# MainCPCB003.net
KiCad netlist of a schematic drawn in EAGLE
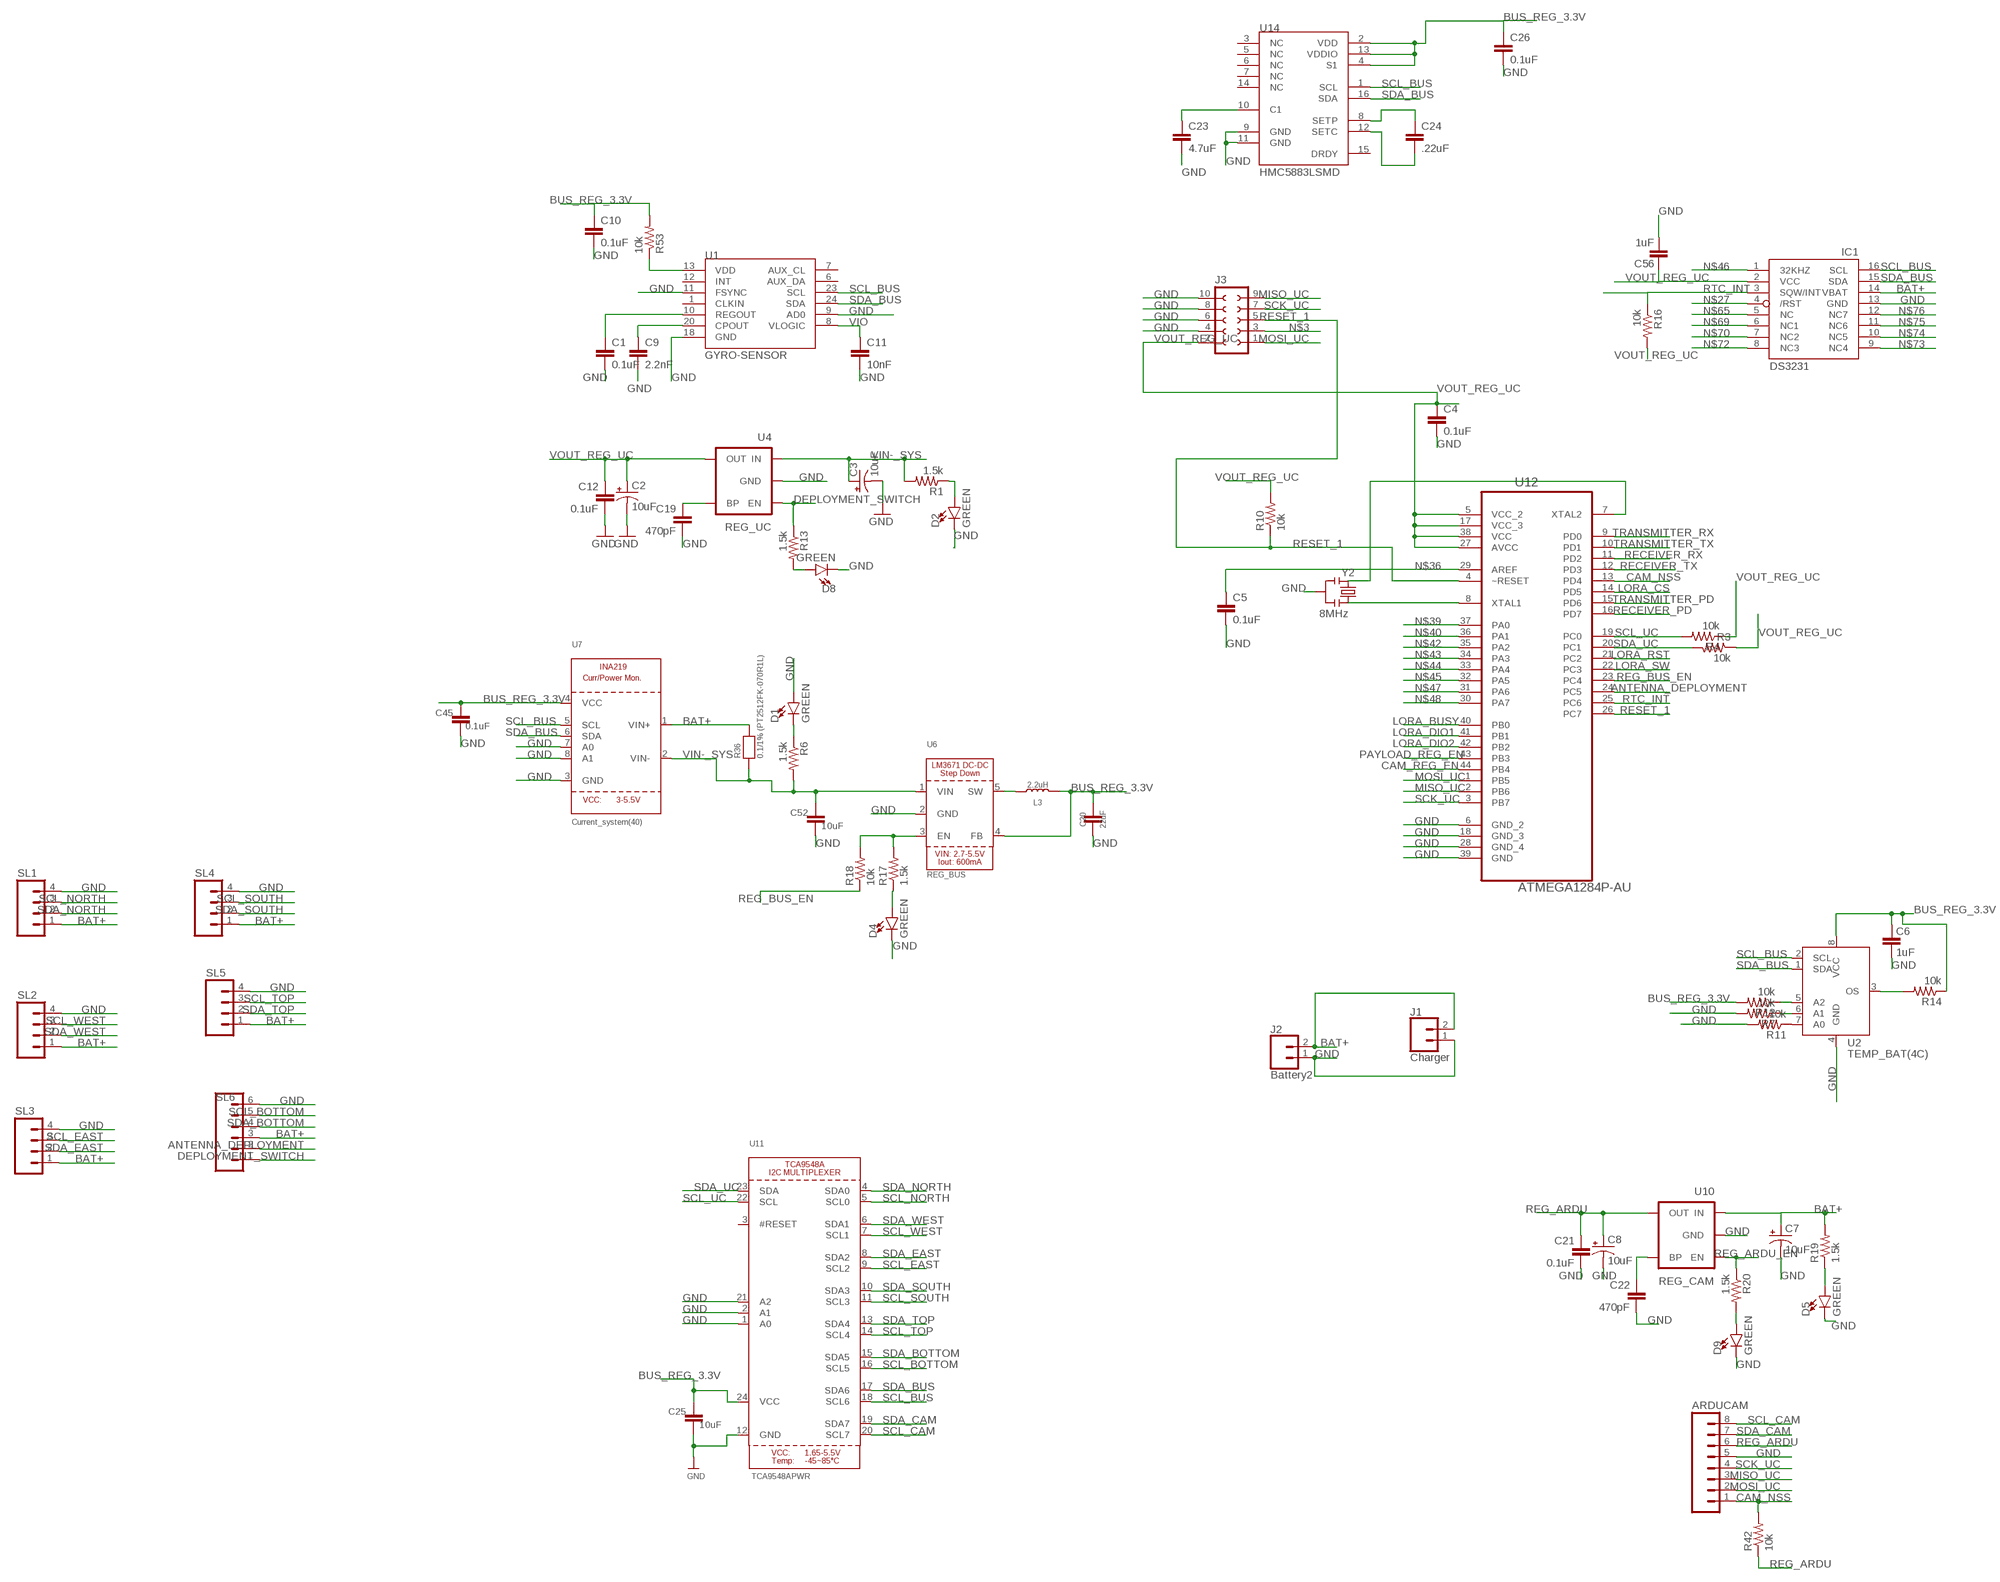
[diagram p0: schematic, sheet 1, part 1 of 2]
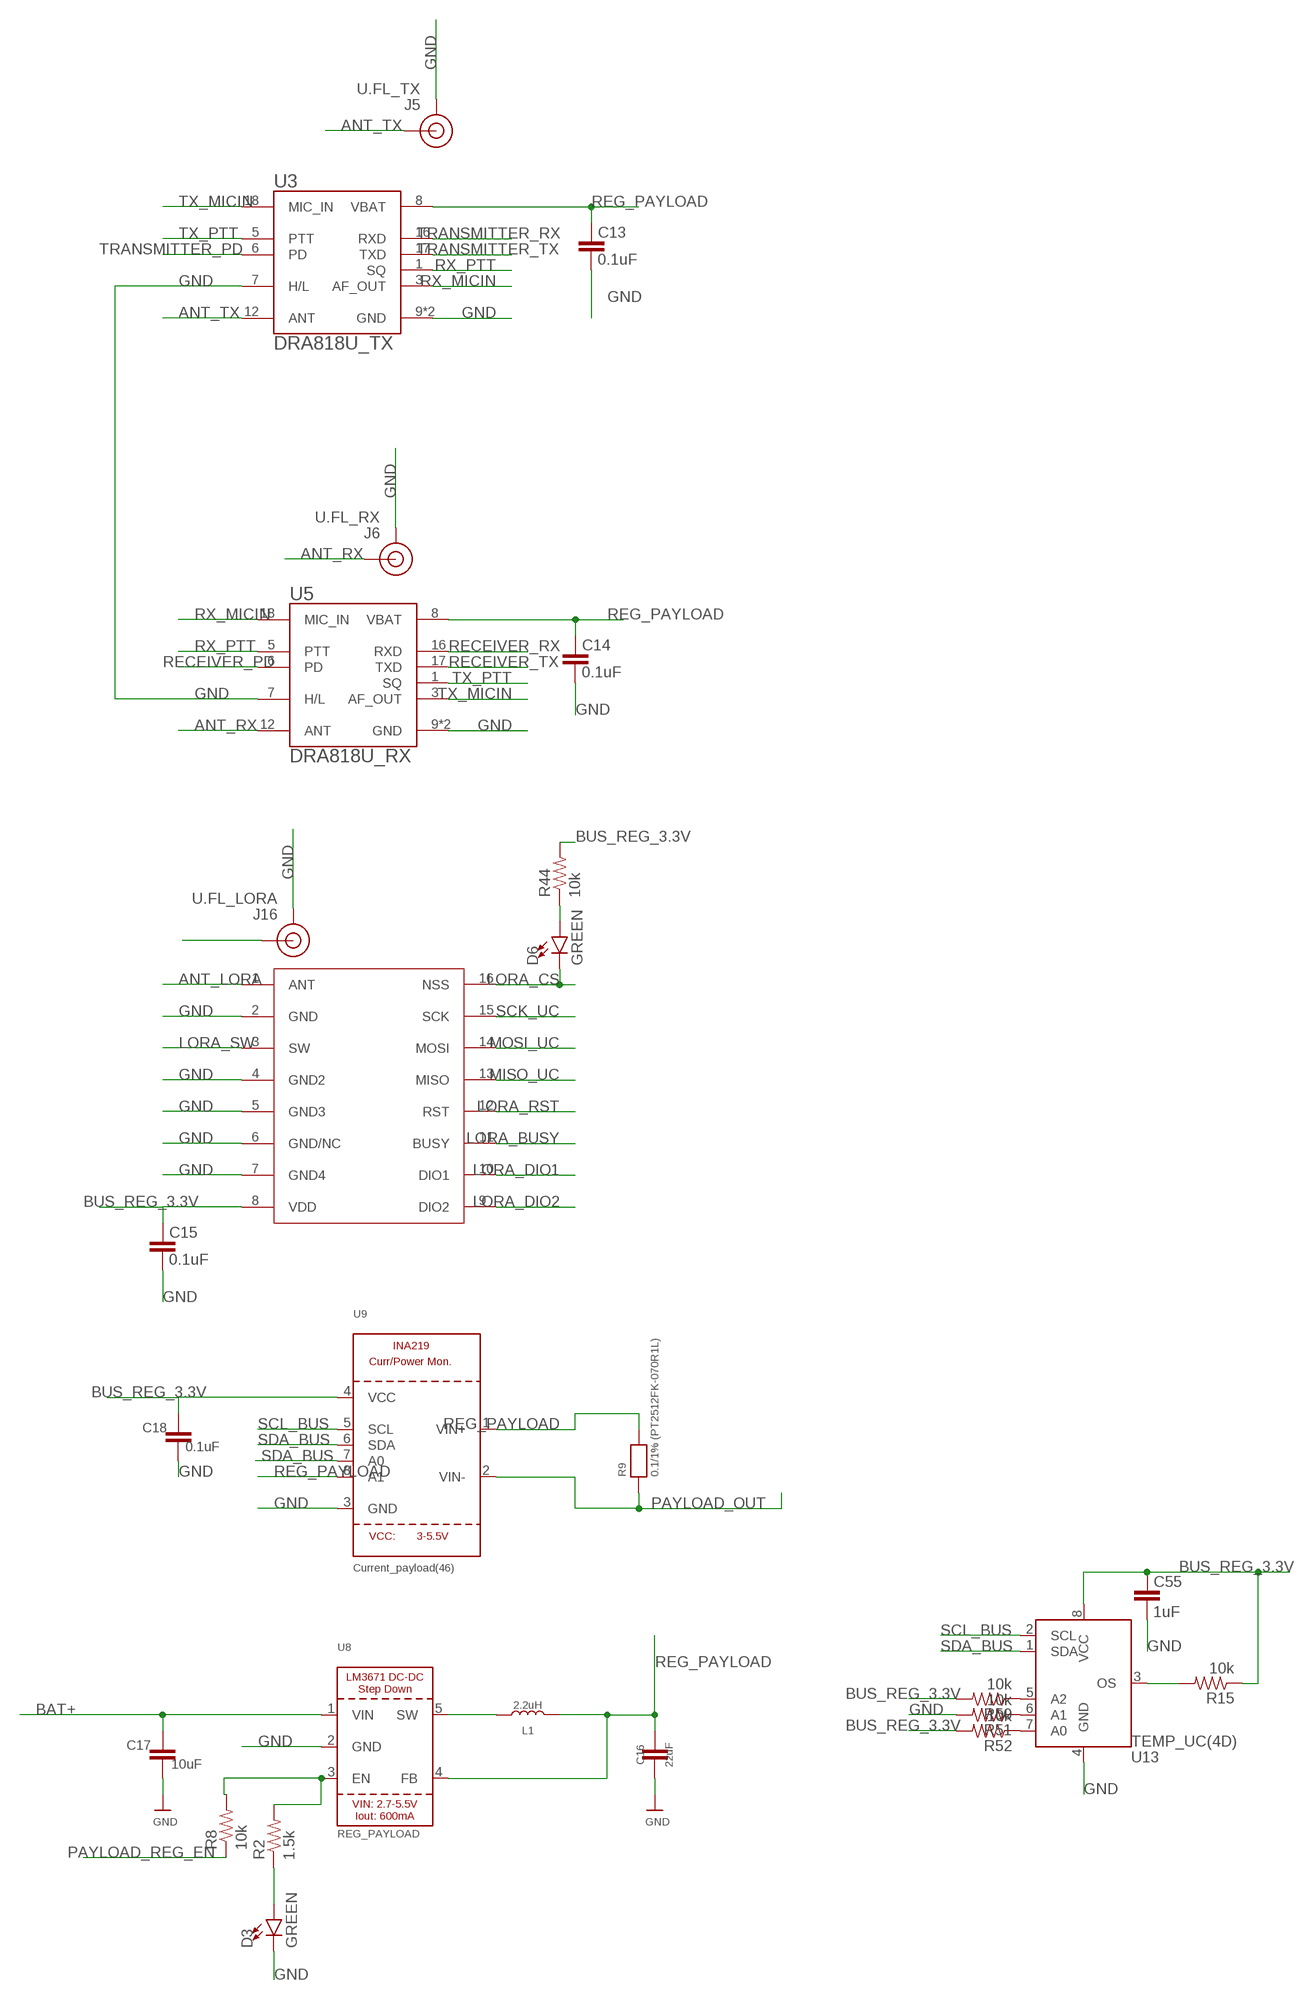
[diagram p1: schematic, sheet 1, part 2 of 2]

(export (version "E")
  (design (tool "Eeschema 10.0.6"))
  (components
    (comp (ref "ARDUCAM")
      (value "M08")
      (footprint "eagle-import:08P")
      (libsource (lib "eagle-import") (part "M08"))
    )
    (comp (ref "C1")
      (value "0.1uF")
      (footprint "eagle-import:0603-CAP")
      (libsource (lib "eagle-import") (part "CAP0603-CAP"))
    )
    (comp (ref "C2")
      (value "10uF")
      (footprint "eagle-import:0603-POLAR")
      (libsource (lib "eagle-import") (part "10UF-POLAR-0603-6.3V-20%(TANT)"))
    )
    (comp (ref "C3")
      (value "10uF")
      (footprint "eagle-import:0603-POLAR")
      (libsource (lib "eagle-import") (part "10UF-POLAR-0603-6.3V-20%(TANT)"))
    )
    (comp (ref "C4")
      (value "0.1uF")
      (footprint "eagle-import:0603-CAP")
      (libsource (lib "eagle-import") (part "CAP0603-CAP"))
    )
    (comp (ref "C5")
      (value "0.1uF")
      (footprint "eagle-import:0603-CAP")
      (libsource (lib "eagle-import") (part "CAP0603-CAP"))
    )
    (comp (ref "C6")
      (value "1uF")
      (footprint "eagle-import:0603-CAP")
      (libsource (lib "eagle-import") (part "CAP0603-CAP"))
    )
    (comp (ref "C7")
      (value "10uF")
      (footprint "eagle-import:0603-POLAR")
      (libsource (lib "eagle-import") (part "10UF-POLAR-0603-6.3V-20%(TANT)"))
    )
    (comp (ref "C8")
      (value "10uF")
      (footprint "eagle-import:0603-POLAR")
      (libsource (lib "eagle-import") (part "10UF-POLAR-0603-6.3V-20%(TANT)"))
    )
    (comp (ref "C9")
      (value "2.2nF")
      (footprint "eagle-import:0603-CAP")
      (libsource (lib "eagle-import") (part "CAP0603-CAP"))
    )
    (comp (ref "C10")
      (value "0.1uF")
      (footprint "eagle-import:0603-CAP")
      (libsource (lib "eagle-import") (part "CAP0603-CAP"))
    )
    (comp (ref "C11")
      (value "10nF")
      (footprint "eagle-import:0603-CAP")
      (libsource (lib "eagle-import") (part "CAP0603-CAP"))
    )
    (comp (ref "C12")
      (value "0.1uF")
      (footprint "eagle-import:0603-CAP")
      (libsource (lib "eagle-import") (part "CAP0603-CAP"))
    )
    (comp (ref "C13")
      (value "0.1uF")
      (footprint "eagle-import:0603-CAP")
      (libsource (lib "eagle-import") (part "CAP0603-CAP"))
    )
    (comp (ref "C14")
      (value "0.1uF")
      (footprint "eagle-import:0603-CAP")
      (libsource (lib "eagle-import") (part "CAP0603-CAP"))
    )
    (comp (ref "C15")
      (value "0.1uF")
      (footprint "eagle-import:0603-CAP")
      (libsource (lib "eagle-import") (part "CAP0603-CAP"))
    )
    (comp (ref "C16")
      (value "22uF")
      (footprint "eagle-import:0603")
      (libsource (lib "eagle-import") (part "10UF-0603-6.3V-20%"))
    )
    (comp (ref "C17")
      (value "10uF")
      (footprint "eagle-import:0603")
      (libsource (lib "eagle-import") (part "10UF-0603-6.3V-20%"))
    )
    (comp (ref "C18")
      (value "0.1uF")
      (footprint "eagle-import:0603")
      (libsource (lib "eagle-import") (part "10UF-0603-6.3V-20%"))
    )
    (comp (ref "C19")
      (value "470pF")
      (footprint "eagle-import:0603-CAP")
      (libsource (lib "eagle-import") (part "CAP0603-CAP"))
    )
    (comp (ref "C20")
      (value "22uF")
      (footprint "eagle-import:0603")
      (libsource (lib "eagle-import") (part "10UF-0603-6.3V-20%"))
    )
    (comp (ref "C21")
      (value "0.1uF")
      (footprint "eagle-import:0603-CAP")
      (libsource (lib "eagle-import") (part "CAP0603-CAP"))
    )
    (comp (ref "C22")
      (value "470pF")
      (footprint "eagle-import:0603-CAP")
      (libsource (lib "eagle-import") (part "CAP0603-CAP"))
    )
    (comp (ref "C23")
      (value "4.7uF")
      (footprint "eagle-import:0603")
      (libsource (lib "eagle-import") (part "0.18UF-0603-10V-10%"))
    )
    (comp (ref "C24")
      (value ".22uF")
      (footprint "eagle-import:0603")
      (libsource (lib "eagle-import") (part "0.18UF-0603-10V-10%"))
    )
    (comp (ref "C25")
      (value "10uF")
      (footprint "eagle-import:0603")
      (libsource (lib "eagle-import") (part "10UF-0603-6.3V-20%"))
    )
    (comp (ref "C26")
      (value "0.1uF")
      (footprint "eagle-import:0603")
      (libsource (lib "eagle-import") (part "0.18UF-0603-10V-10%"))
    )
    (comp (ref "C45")
      (value "0.1uF")
      (footprint "eagle-import:0603")
      (libsource (lib "eagle-import") (part "10UF-0603-6.3V-20%"))
    )
    (comp (ref "C52")
      (value "10uF")
      (footprint "eagle-import:0603")
      (libsource (lib "eagle-import") (part "10UF-0603-6.3V-20%"))
    )
    (comp (ref "C55")
      (value "1uF")
      (footprint "eagle-import:0603-CAP")
      (libsource (lib "eagle-import") (part "CAP0603-CAP"))
    )
    (comp (ref "C56")
      (value "1uF")
      (footprint "eagle-import:0603-CAP")
      (libsource (lib "eagle-import") (part "CAP0603-CAP"))
    )
    (comp (ref "D1")
      (value "GREEN")
      (footprint "eagle-import:LED-0603")
      (libsource (lib "eagle-import") (part "LED-GREEN0603"))
    )
    (comp (ref "D2")
      (value "GREEN")
      (footprint "eagle-import:LED-0603")
      (libsource (lib "eagle-import") (part "LED-GREEN0603"))
    )
    (comp (ref "D3")
      (value "GREEN")
      (footprint "eagle-import:LED-0603")
      (libsource (lib "eagle-import") (part "LED-GREEN0603"))
    )
    (comp (ref "D4")
      (value "GREEN")
      (footprint "eagle-import:LED-0603")
      (libsource (lib "eagle-import") (part "LED-GREEN0603"))
    )
    (comp (ref "D5")
      (value "GREEN")
      (footprint "eagle-import:LED-0603")
      (libsource (lib "eagle-import") (part "LED-GREEN0603"))
    )
    (comp (ref "D6")
      (value "GREEN")
      (footprint "eagle-import:LED-0603")
      (libsource (lib "eagle-import") (part "LED-GREEN0603"))
    )
    (comp (ref "D8")
      (value "GREEN")
      (footprint "eagle-import:LED-0603")
      (libsource (lib "eagle-import") (part "LED-GREEN0603"))
    )
    (comp (ref "D9")
      (value "GREEN")
      (footprint "eagle-import:LED-0603")
      (libsource (lib "eagle-import") (part "LED-GREEN0603"))
    )
    (comp (ref "IC1")
      (value "DS3231/SO")
      (footprint "eagle-import:SO16W")
      (fields (field (name "MF") "Maxim Integrated") (field (name "MP") "DS3231"))
      (libsource (lib "eagle-import") (part "DS3231/SO"))
    )
    (comp (ref "J1")
      (value "Charger")
      (footprint "eagle-import:1X02")
      (libsource (lib "eagle-import") (part "CONN_02"))
    )
    (comp (ref "J2")
      (value "Battery2")
      (footprint "eagle-import:1X02")
      (libsource (lib "eagle-import") (part "CONN_02"))
    )
    (comp (ref "J3")
      (value "SOCKET-10V")
      (footprint "eagle-import:S10V")
      (libsource (lib "eagle-import") (part "SOCKET-10V"))
    )
    (comp (ref "J5")
      (value "U.FL_TX")
      (footprint "eagle-import:U.FL")
      (libsource (lib "eagle-import") (part "U.FL2PIN"))
    )
    (comp (ref "J6")
      (value "U.FL_RX")
      (footprint "eagle-import:U.FL")
      (libsource (lib "eagle-import") (part "U.FL2PIN"))
    )
    (comp (ref "J16")
      (value "U.FL_LORA")
      (footprint "eagle-import:U.FL")
      (libsource (lib "eagle-import") (part "U.FL2PIN"))
    )
    (comp (ref "L1")
      (value "2.2uH")
      (footprint "eagle-import:0603")
      (libsource (lib "eagle-import") (part "INDUCTOR-0603-33NH"))
    )
    (comp (ref "L3")
      (value "2.2uH")
      (footprint "eagle-import:0603")
      (libsource (lib "eagle-import") (part "INDUCTOR-0603-33NH"))
    )
    (comp (ref "R1")
      (value "1.5k")
      (footprint "eagle-import:0603-RES")
      (libsource (lib "eagle-import") (part "RESISTOR0603-RES"))
    )
    (comp (ref "R2")
      (value "1.5k")
      (footprint "eagle-import:0603-RES")
      (libsource (lib "eagle-import") (part "RESISTOR0603-RES"))
    )
    (comp (ref "R3")
      (value "10k")
      (footprint "eagle-import:0603-RES")
      (libsource (lib "eagle-import") (part "RESISTOR0603-RES"))
    )
    (comp (ref "R4")
      (value "10k")
      (footprint "eagle-import:0603-RES")
      (libsource (lib "eagle-import") (part "RESISTOR0603-RES"))
    )
    (comp (ref "R6")
      (value "1.5k")
      (footprint "eagle-import:0603-RES")
      (libsource (lib "eagle-import") (part "RESISTOR0603-RES"))
    )
    (comp (ref "R7")
      (value "10k")
      (footprint "eagle-import:0603-RES")
      (libsource (lib "eagle-import") (part "RESISTOR0603-RES"))
    )
    (comp (ref "R8")
      (value "10k")
      (footprint "eagle-import:0402-RES")
      (libsource (lib "eagle-import") (part "RESISTOR0402-RES"))
    )
    (comp (ref "R9")
      (value "0.1/1% (PT2512FK-070R1L)")
      (footprint "eagle-import:2512")
      (libsource (lib "eagle-import") (part "microbuilder_RESISTOR2512"))
    )
    (comp (ref "R10")
      (value "10k")
      (footprint "eagle-import:0402-RES")
      (libsource (lib "eagle-import") (part "RESISTOR0402-RES"))
    )
    (comp (ref "R11")
      (value "10k")
      (footprint "eagle-import:0603-RES")
      (libsource (lib "eagle-import") (part "RESISTOR0603-RES"))
    )
    (comp (ref "R12")
      (value "10k")
      (footprint "eagle-import:0603-RES")
      (libsource (lib "eagle-import") (part "RESISTOR0603-RES"))
    )
    (comp (ref "R13")
      (value "1.5k")
      (footprint "eagle-import:0603-RES")
      (libsource (lib "eagle-import") (part "RESISTOR0603-RES"))
    )
    (comp (ref "R14")
      (value "10k")
      (footprint "eagle-import:0603-RES")
      (libsource (lib "eagle-import") (part "RESISTOR0603-RES"))
    )
    (comp (ref "R15")
      (value "10k")
      (footprint "eagle-import:0603-RES")
      (libsource (lib "eagle-import") (part "RESISTOR0603-RES"))
    )
    (comp (ref "R16")
      (value "10k")
      (footprint "eagle-import:0603-RES")
      (libsource (lib "eagle-import") (part "RESISTOR0603-RES"))
    )
    (comp (ref "R17")
      (value "1.5k")
      (footprint "eagle-import:0603-RES")
      (libsource (lib "eagle-import") (part "RESISTOR0603-RES"))
    )
    (comp (ref "R18")
      (value "10k")
      (footprint "eagle-import:0603-RES")
      (libsource (lib "eagle-import") (part "RESISTOR0603-RES"))
    )
    (comp (ref "R19")
      (value "1.5k")
      (footprint "eagle-import:0603-RES")
      (libsource (lib "eagle-import") (part "RESISTOR0603-RES"))
    )
    (comp (ref "R20")
      (value "1.5k")
      (footprint "eagle-import:0603-RES")
      (libsource (lib "eagle-import") (part "RESISTOR0603-RES"))
    )
    (comp (ref "R36")
      (value "0.1/1% (PT2512FK-070R1L)")
      (footprint "eagle-import:2512")
      (libsource (lib "eagle-import") (part "microbuilder_RESISTOR2512"))
    )
    (comp (ref "R42")
      (value "10k")
      (footprint "eagle-import:0603-RES")
      (libsource (lib "eagle-import") (part "RESISTOR0603-RES"))
    )
    (comp (ref "R44")
      (value "10k")
      (footprint "eagle-import:0603-RES")
      (libsource (lib "eagle-import") (part "RESISTOR0603-RES"))
    )
    (comp (ref "R50")
      (value "10k")
      (footprint "eagle-import:0603-RES")
      (libsource (lib "eagle-import") (part "RESISTOR0603-RES"))
    )
    (comp (ref "R51")
      (value "10k")
      (footprint "eagle-import:0603-RES")
      (libsource (lib "eagle-import") (part "RESISTOR0603-RES"))
    )
    (comp (ref "R52")
      (value "10k")
      (footprint "eagle-import:0603-RES")
      (libsource (lib "eagle-import") (part "RESISTOR0603-RES"))
    )
    (comp (ref "R53")
      (value "10k")
      (footprint "eagle-import:0603-RES")
      (libsource (lib "eagle-import") (part "RESISTOR0603-RES"))
    )
    (comp (ref "SL1")
      (value "M04")
      (footprint "eagle-import:04P")
      (libsource (lib "eagle-import") (part "M04"))
    )
    (comp (ref "SL2")
      (value "M04")
      (footprint "eagle-import:04P")
      (libsource (lib "eagle-import") (part "M04"))
    )
    (comp (ref "SL3")
      (value "M04")
      (footprint "eagle-import:04P")
      (libsource (lib "eagle-import") (part "M04"))
    )
    (comp (ref "SL4")
      (value "M04")
      (footprint "eagle-import:04P")
      (libsource (lib "eagle-import") (part "M04"))
    )
    (comp (ref "SL5")
      (value "M04")
      (footprint "eagle-import:04P")
      (libsource (lib "eagle-import") (part "M04"))
    )
    (comp (ref "SL6")
      (value "M06")
      (footprint "eagle-import:06P")
      (libsource (lib "eagle-import") (part "M06"))
    )
    (comp (ref "U$1")
      (value "DRF1268")
      (footprint "eagle-import:RESCAV180P1570X1400X300-16")
      (libsource (lib "eagle-import") (part "DRF1268"))
    )
    (comp (ref "U1")
      (value "GYRO-SENSOR")
      (footprint "eagle-import:QFN-24-4MM2")
      (libsource (lib "eagle-import") (part "MPU-6050-1"))
    )
    (comp (ref "U2")
      (value "TEMP_BAT(4C)")
      (footprint "eagle-import:SOT505-1")
      (fields (field (name "MF") "NXP Semiconductors") (field (name "MP") "LM75B"))
      (libsource (lib "eagle-import") (part "LM75BDP"))
    )
    (comp (ref "U3")
      (value "DRA818U_TX")
      (footprint "eagle-import:DORJI_DRA818U")
      (fields (field (name "MF") "DORJI") (field (name "MP") "DRA818V"))
      (libsource (lib "eagle-import") (part "DRA818U"))
    )
    (comp (ref "U4")
      (value "REG_UC")
      (footprint "eagle-import:SOT23-5")
      (libsource (lib "eagle-import") (part "V_REG_LDOSMD"))
    )
    (comp (ref "U5")
      (value "DRA818U_RX")
      (footprint "eagle-import:DORJI_DRA818U")
      (fields (field (name "MF") "DORJI") (field (name "MP") "DRA818V"))
      (libsource (lib "eagle-import") (part "DRA818U"))
    )
    (comp (ref "U6")
      (value "REG_BUS")
      (footprint "eagle-import:SOT23-5")
      (libsource (lib "eagle-import") (part "VREG_LM3671"))
    )
    (comp (ref "U7")
      (value "Current_system(40)")
      (footprint "eagle-import:SOT23-8")
      (libsource (lib "eagle-import") (part "INA219"))
    )
    (comp (ref "U8")
      (value "REG_PAYLOAD")
      (footprint "eagle-import:SOT23-5")
      (libsource (lib "eagle-import") (part "VREG_LM3671"))
    )
    (comp (ref "U9")
      (value "Current_payload(46)")
      (footprint "eagle-import:SOT23-8")
      (libsource (lib "eagle-import") (part "INA219"))
    )
    (comp (ref "U10")
      (value "REG_CAM")
      (footprint "eagle-import:SOT23-5")
      (libsource (lib "eagle-import") (part "V_REG_LDOSMD"))
    )
    (comp (ref "U11")
      (value "TCA9548APWR")
      (footprint "eagle-import:TSSOP24")
      (libsource (lib "eagle-import") (part "TCA9548A"))
    )
    (comp (ref "U12")
      (value "ATMEGA1284P-AU")
      (footprint "eagle-import:QFP80P1200X1200X120-44N")
      (fields (field (name "MF") "Microchip"))
      (libsource (lib "eagle-import") (part "ATMEGA1284P-AU"))
    )
    (comp (ref "U13")
      (value "TEMP_UC(4D)")
      (footprint "eagle-import:SOT505-1")
      (fields (field (name "MF") "NXP Semiconductors") (field (name "MP") "LM75B"))
      (libsource (lib "eagle-import") (part "LM75BDP"))
    )
    (comp (ref "U14")
      (value "HMC5883LSMD")
      (footprint "eagle-import:16LPCC")
      (libsource (lib "eagle-import") (part "HMC5883LSMD"))
    )
    (comp (ref "Y2")
      (value "RESONATORSMD")
      (footprint "eagle-import:RESONATOR-SMD")
      (libsource (lib "eagle-import") (part "RESONATORSMD"))
    )
  )
  (nets
    (net (code "1") (name "/ANTENNA_DEPLOYMENT") (class "Default")
      (node (ref "SL6") (pin "2") (pinfunction "2_2") (pintype "passive"))
      (node (ref "U12") (pin "24") (pinfunction "PC5_24") (pintype "bidirectional"))
    )
    (net (code "2") (name "/ANT_LORA") (class "Default")
      (node (ref "J16") (pin "FEED") (pinfunction "SIGNAL_FEED") (pintype "bidirectional"))
      (node (ref "U$1") (pin "1") (pinfunction "ANT_1") (pintype "bidirectional"))
    )
    (net (code "3") (name "/ANT_RX") (class "Default")
      (node (ref "J6") (pin "FEED") (pinfunction "SIGNAL_FEED") (pintype "bidirectional"))
      (node (ref "U5") (pin "12") (pinfunction "ANT_12") (pintype "passive"))
    )
    (net (code "4") (name "/ANT_TX") (class "Default")
      (node (ref "J5") (pin "FEED") (pinfunction "SIGNAL_FEED") (pintype "bidirectional"))
      (node (ref "U3") (pin "12") (pinfunction "ANT_12") (pintype "passive"))
    )
    (net (code "5") (name "/BAT+") (class "Default")
      (node (ref "C17") (pin "1") (pinfunction "1_1") (pintype "passive"))
      (node (ref "C7") (pin "+") (pinfunction "+_+") (pintype "passive"))
      (node (ref "IC1") (pin "14") (pinfunction "VBAT_14") (pintype "power_in"))
      (node (ref "J1") (pin "2") (pinfunction "2_2") (pintype "passive"))
      (node (ref "J2") (pin "2") (pinfunction "2_2") (pintype "passive"))
      (node (ref "R19") (pin "2") (pinfunction "2_2") (pintype "passive"))
      (node (ref "R36") (pin "2") (pinfunction "2_2") (pintype "passive"))
      (node (ref "SL1") (pin "1") (pinfunction "1_1") (pintype "passive"))
      (node (ref "SL2") (pin "1") (pinfunction "1_1") (pintype "passive"))
      (node (ref "SL3") (pin "1") (pinfunction "1_1") (pintype "passive"))
      (node (ref "SL4") (pin "1") (pinfunction "1_1") (pintype "passive"))
      (node (ref "SL5") (pin "1") (pinfunction "1_1") (pintype "passive"))
      (node (ref "SL6") (pin "3") (pinfunction "3_3") (pintype "passive"))
      (node (ref "U10") (pin "1") (pinfunction "IN_1") (pintype "input"))
      (node (ref "U7") (pin "1") (pinfunction "VIN+_1") (pintype "bidirectional"))
      (node (ref "U8") (pin "1") (pinfunction "VIN_1") (pintype "power_in"))
    )
    (net (code "6") (name "/BUS_REG_3.3V") (class "Default")
      (node (ref "C10") (pin "1") (pinfunction "1_1") (pintype "passive"))
      (node (ref "C15") (pin "2") (pinfunction "2_2") (pintype "passive"))
      (node (ref "C18") (pin "1") (pinfunction "1_1") (pintype "passive"))
      (node (ref "C20") (pin "1") (pinfunction "1_1") (pintype "passive"))
      (node (ref "C25") (pin "1") (pinfunction "1_1") (pintype "passive"))
      (node (ref "C26") (pin "1") (pinfunction "1_1") (pintype "passive"))
      (node (ref "C45") (pin "1") (pinfunction "1_1") (pintype "passive"))
      (node (ref "C55") (pin "2") (pinfunction "2_2") (pintype "passive"))
      (node (ref "C6") (pin "2") (pinfunction "2_2") (pintype "passive"))
      (node (ref "L3") (pin "2") (pinfunction "2_2") (pintype "passive"))
      (node (ref "R12") (pin "2") (pinfunction "2_2") (pintype "passive"))
      (node (ref "R14") (pin "1") (pinfunction "1_1") (pintype "passive"))
      (node (ref "R15") (pin "1") (pinfunction "1_1") (pintype "passive"))
      (node (ref "R44") (pin "2") (pinfunction "2_2") (pintype "passive"))
      (node (ref "R50") (pin "2") (pinfunction "2_2") (pintype "passive"))
      (node (ref "R52") (pin "2") (pinfunction "2_2") (pintype "passive"))
      (node (ref "R53") (pin "2") (pinfunction "2_2") (pintype "passive"))
      (node (ref "U$1") (pin "8") (pinfunction "VDD_8") (pintype "bidirectional"))
      (node (ref "U11") (pin "24") (pinfunction "VCC_24") (pintype "bidirectional"))
      (node (ref "U13") (pin "8") (pinfunction "VCC_8") (pintype "power_in"))
      (node (ref "U14") (pin "13") (pinfunction "VDDIO_13") (pintype "bidirectional"))
      (node (ref "U14") (pin "2") (pinfunction "VDD_2") (pintype "bidirectional"))
      (node (ref "U14") (pin "4") (pinfunction "S1_4") (pintype "bidirectional"))
      (node (ref "U2") (pin "8") (pinfunction "VCC_8") (pintype "power_in"))
      (node (ref "U6") (pin "4") (pinfunction "FB_4") (pintype "power_in"))
      (node (ref "U7") (pin "4") (pinfunction "VCC_4") (pintype "bidirectional"))
      (node (ref "U9") (pin "4") (pinfunction "VCC_4") (pintype "bidirectional"))
    )
    (net (code "7") (name "/CAM_NSS") (class "Default")
      (node (ref "ARDUCAM") (pin "1") (pinfunction "1_1") (pintype "passive"))
      (node (ref "R42") (pin "2") (pinfunction "2_2") (pintype "passive"))
      (node (ref "U12") (pin "13") (pinfunction "PD4_13") (pintype "bidirectional"))
    )
    (net (code "8") (name "/CAM_REG_EN") (class "Default")
      (node (ref "U12") (pin "44") (pinfunction "PB4_44") (pintype "bidirectional"))
    )
    (net (code "9") (name "/DEPLOYMENT_SWITCH") (class "Default")
      (node (ref "R13") (pin "1") (pinfunction "1_1") (pintype "passive"))
      (node (ref "SL6") (pin "1") (pinfunction "1_1") (pintype "passive"))
      (node (ref "U4") (pin "3") (pinfunction "EN_3") (pintype "input"))
    )
    (net (code "10") (name "/LORA_BUSY") (class "Default")
      (node (ref "U$1") (pin "11") (pinfunction "BUSY_11") (pintype "bidirectional"))
      (node (ref "U12") (pin "40") (pinfunction "PB0_40") (pintype "bidirectional"))
    )
    (net (code "11") (name "/LORA_CS") (class "Default")
      (node (ref "D6") (pin "C") (pinfunction "C_C") (pintype "passive"))
      (node (ref "U$1") (pin "16") (pinfunction "NSS_16") (pintype "bidirectional"))
      (node (ref "U12") (pin "14") (pinfunction "PD5_14") (pintype "bidirectional"))
    )
    (net (code "12") (name "/LORA_DIO1") (class "Default")
      (node (ref "U$1") (pin "10") (pinfunction "DIO1_10") (pintype "bidirectional"))
      (node (ref "U12") (pin "41") (pinfunction "PB1_41") (pintype "bidirectional"))
    )
    (net (code "13") (name "/LORA_DIO2") (class "Default")
      (node (ref "U$1") (pin "9") (pinfunction "DIO2_9") (pintype "bidirectional"))
      (node (ref "U12") (pin "42") (pinfunction "PB2_42") (pintype "bidirectional"))
    )
    (net (code "14") (name "/LORA_RST") (class "Default")
      (node (ref "U$1") (pin "12") (pinfunction "RST_12") (pintype "bidirectional"))
      (node (ref "U12") (pin "21") (pinfunction "PC2_21") (pintype "bidirectional"))
    )
    (net (code "15") (name "/LORA_SW") (class "Default")
      (node (ref "U$1") (pin "3") (pinfunction "SW_3") (pintype "bidirectional"))
      (node (ref "U12") (pin "22") (pinfunction "PC3_22") (pintype "bidirectional"))
    )
    (net (code "16") (name "/MISO_UC") (class "Default")
      (node (ref "ARDUCAM") (pin "3") (pinfunction "3_3") (pintype "passive"))
      (node (ref "J3") (pin "9") (pinfunction "9_9") (pintype "passive"))
      (node (ref "U$1") (pin "13") (pinfunction "MISO_13") (pintype "bidirectional"))
      (node (ref "U12") (pin "2") (pinfunction "PB6_2") (pintype "bidirectional"))
    )
    (net (code "17") (name "/MOSI_UC") (class "Default")
      (node (ref "ARDUCAM") (pin "2") (pinfunction "2_2") (pintype "passive"))
      (node (ref "J3") (pin "1") (pinfunction "1_1") (pintype "passive"))
      (node (ref "U$1") (pin "14") (pinfunction "MOSI_14") (pintype "bidirectional"))
      (node (ref "U12") (pin "1") (pinfunction "PB5_1") (pintype "bidirectional"))
    )
    (net (code "18") (name "/N$3") (class "Default")
      (node (ref "J3") (pin "3") (pinfunction "3_3") (pintype "passive"))
    )
    (net (code "19") (name "/N$27") (class "Default")
      (node (ref "IC1") (pin "4") (pinfunction "/RST_4") (pintype "passive"))
    )
    (net (code "20") (name "/N$36") (class "Default")
      (node (ref "C5") (pin "1") (pinfunction "1_1") (pintype "passive"))
      (node (ref "U12") (pin "29") (pinfunction "AREF_29") (pintype "input"))
    )
    (net (code "21") (name "/N$39") (class "Default")
      (node (ref "U12") (pin "37") (pinfunction "PA0_37") (pintype "bidirectional"))
    )
    (net (code "22") (name "/N$40") (class "Default")
      (node (ref "U12") (pin "36") (pinfunction "PA1_36") (pintype "bidirectional"))
    )
    (net (code "23") (name "/N$42") (class "Default")
      (node (ref "U12") (pin "35") (pinfunction "PA2_35") (pintype "bidirectional"))
    )
    (net (code "24") (name "/N$43") (class "Default")
      (node (ref "U12") (pin "34") (pinfunction "PA3_34") (pintype "bidirectional"))
    )
    (net (code "25") (name "/N$44") (class "Default")
      (node (ref "U12") (pin "33") (pinfunction "PA4_33") (pintype "bidirectional"))
    )
    (net (code "26") (name "/N$45") (class "Default")
      (node (ref "U12") (pin "32") (pinfunction "PA5_32") (pintype "bidirectional"))
    )
    (net (code "27") (name "/N$46") (class "Default")
      (node (ref "IC1") (pin "1") (pinfunction "32KHZ_1") (pintype "output"))
    )
    (net (code "28") (name "/N$47") (class "Default")
      (node (ref "U12") (pin "31") (pinfunction "PA6_31") (pintype "bidirectional"))
    )
    (net (code "29") (name "/N$48") (class "Default")
      (node (ref "U12") (pin "30") (pinfunction "PA7_30") (pintype "bidirectional"))
    )
    (net (code "38") (name "/PAYLOAD_OUT") (class "Default")
      (node (ref "R9") (pin "1") (pinfunction "1_1") (pintype "passive"))
      (node (ref "U9") (pin "2") (pinfunction "VIN-_2") (pintype "bidirectional"))
    )
    (net (code "39") (name "/PAYLOAD_REG_EN") (class "Default")
      (node (ref "R8") (pin "1") (pinfunction "1_1") (pintype "passive"))
      (node (ref "U12") (pin "43") (pinfunction "PB3_43") (pintype "bidirectional"))
    )
    (net (code "40") (name "/RECEIVER_PD") (class "Default")
      (node (ref "U12") (pin "16") (pinfunction "PD7_16") (pintype "bidirectional"))
      (node (ref "U5") (pin "6") (pinfunction "PD_6") (pintype "input"))
    )
    (net (code "41") (name "/RECEIVER_RX") (class "Default")
      (node (ref "U12") (pin "11") (pinfunction "PD2_11") (pintype "bidirectional"))
      (node (ref "U5") (pin "16") (pinfunction "RXD_16") (pintype "input"))
    )
    (net (code "42") (name "/RECEIVER_TX") (class "Default")
      (node (ref "U12") (pin "12") (pinfunction "PD3_12") (pintype "bidirectional"))
      (node (ref "U5") (pin "17") (pinfunction "TXD_17") (pintype "output"))
    )
    (net (code "43") (name "/REG_ARDU") (class "Default")
      (node (ref "ARDUCAM") (pin "6") (pinfunction "6_6") (pintype "passive"))
      (node (ref "C21") (pin "1") (pinfunction "1_1") (pintype "passive"))
      (node (ref "C8") (pin "+") (pinfunction "+_+") (pintype "passive"))
      (node (ref "R42") (pin "1") (pinfunction "1_1") (pintype "passive"))
      (node (ref "U10") (pin "5") (pinfunction "OUT_5") (pintype "passive"))
    )
    (net (code "44") (name "/REG_ARDU_EN") (class "Default")
      (node (ref "R20") (pin "1") (pinfunction "1_1") (pintype "passive"))
      (node (ref "U10") (pin "3") (pinfunction "EN_3") (pintype "input"))
    )
    (net (code "45") (name "/REG_BUS_EN") (class "Default")
      (node (ref "R18") (pin "1") (pinfunction "1_1") (pintype "passive"))
      (node (ref "U12") (pin "23") (pinfunction "PC4_23") (pintype "bidirectional"))
    )
    (net (code "46") (name "/REG_PAYLOAD") (class "Default")
      (node (ref "C13") (pin "2") (pinfunction "2_2") (pintype "passive"))
      (node (ref "C14") (pin "2") (pinfunction "2_2") (pintype "passive"))
      (node (ref "C16") (pin "1") (pinfunction "1_1") (pintype "passive"))
      (node (ref "L1") (pin "2") (pinfunction "2_2") (pintype "passive"))
      (node (ref "R9") (pin "2") (pinfunction "2_2") (pintype "passive"))
      (node (ref "U3") (pin "8") (pinfunction "VBAT_8") (pintype "power_in"))
      (node (ref "U5") (pin "8") (pinfunction "VBAT_8") (pintype "power_in"))
      (node (ref "U8") (pin "4") (pinfunction "FB_4") (pintype "power_in"))
      (node (ref "U9") (pin "1") (pinfunction "VIN+_1") (pintype "bidirectional"))
      (node (ref "U9") (pin "8") (pinfunction "A1_8") (pintype "bidirectional"))
    )
    (net (code "47") (name "/RESET_1") (class "Default")
      (node (ref "J3") (pin "5") (pinfunction "5_5") (pintype "passive"))
      (node (ref "R10") (pin "1") (pinfunction "1_1") (pintype "passive"))
      (node (ref "U12") (pin "26") (pinfunction "PC7_26") (pintype "bidirectional"))
      (node (ref "U12") (pin "4") (pinfunction "~{RESET}_4") (pintype "input"))
    )
    (net (code "48") (name "/RTC_INT") (class "Default")
      (node (ref "IC1") (pin "3") (pinfunction "SQW/INT_3") (pintype "output"))
      (node (ref "R16") (pin "1") (pinfunction "1_1") (pintype "passive"))
      (node (ref "U12") (pin "25") (pinfunction "PC6_25") (pintype "bidirectional"))
    )
    (net (code "49") (name "/RX_MICIN") (class "Default")
      (node (ref "U3") (pin "3") (pinfunction "AF_OUT_3") (pintype "output"))
      (node (ref "U5") (pin "18") (pinfunction "MIC_IN_18") (pintype "input"))
    )
    (net (code "50") (name "/RX_PTT") (class "Default")
      (node (ref "U3") (pin "1") (pinfunction "SQ_1") (pintype "output"))
      (node (ref "U5") (pin "5") (pinfunction "PTT_5") (pintype "input"))
    )
    (net (code "51") (name "/SCK_UC") (class "Default")
      (node (ref "ARDUCAM") (pin "4") (pinfunction "4_4") (pintype "passive"))
      (node (ref "J3") (pin "7") (pinfunction "7_7") (pintype "passive"))
      (node (ref "U$1") (pin "15") (pinfunction "SCK_15") (pintype "bidirectional"))
      (node (ref "U12") (pin "3") (pinfunction "PB7_3") (pintype "bidirectional"))
    )
    (net (code "52") (name "/SCL_BOTTOM") (class "Default")
      (node (ref "SL6") (pin "5") (pinfunction "5_5") (pintype "passive"))
      (node (ref "U11") (pin "16") (pinfunction "SCL5_16") (pintype "bidirectional"))
    )
    (net (code "53") (name "/SCL_BUS") (class "Default")
      (node (ref "IC1") (pin "16") (pinfunction "SCL_16") (pintype "bidirectional"))
      (node (ref "U1") (pin "23") (pinfunction "SCL_23") (pintype "bidirectional"))
      (node (ref "U11") (pin "18") (pinfunction "SCL6_18") (pintype "bidirectional"))
      (node (ref "U13") (pin "2") (pinfunction "SCL_2") (pintype "bidirectional"))
      (node (ref "U14") (pin "1") (pinfunction "SCL_1") (pintype "bidirectional"))
      (node (ref "U2") (pin "2") (pinfunction "SCL_2") (pintype "bidirectional"))
      (node (ref "U7") (pin "5") (pinfunction "SCL_5") (pintype "bidirectional"))
      (node (ref "U9") (pin "5") (pinfunction "SCL_5") (pintype "bidirectional"))
    )
    (net (code "54") (name "/SCL_CAM") (class "Default")
      (node (ref "ARDUCAM") (pin "8") (pinfunction "8_8") (pintype "passive"))
      (node (ref "U11") (pin "20") (pinfunction "SCL7_20") (pintype "bidirectional"))
    )
    (net (code "55") (name "/SCL_EAST") (class "Default")
      (node (ref "SL3") (pin "3") (pinfunction "3_3") (pintype "passive"))
      (node (ref "U11") (pin "9") (pinfunction "SCL2_9") (pintype "bidirectional"))
    )
    (net (code "56") (name "/SCL_NORTH") (class "Default")
      (node (ref "SL1") (pin "3") (pinfunction "3_3") (pintype "passive"))
      (node (ref "U11") (pin "5") (pinfunction "SCL0_5") (pintype "bidirectional"))
    )
    (net (code "57") (name "/SCL_SOUTH") (class "Default")
      (node (ref "SL4") (pin "3") (pinfunction "3_3") (pintype "passive"))
      (node (ref "U11") (pin "11") (pinfunction "SCL3_11") (pintype "bidirectional"))
    )
    (net (code "58") (name "/SCL_TOP") (class "Default")
      (node (ref "SL5") (pin "3") (pinfunction "3_3") (pintype "passive"))
      (node (ref "U11") (pin "14") (pinfunction "SCL4_14") (pintype "bidirectional"))
    )
    (net (code "59") (name "/SCL_UC") (class "Default")
      (node (ref "R4") (pin "2") (pinfunction "2_2") (pintype "passive"))
      (node (ref "U11") (pin "22") (pinfunction "SCL_22") (pintype "bidirectional"))
      (node (ref "U12") (pin "19") (pinfunction "PC0_19") (pintype "bidirectional"))
    )
    (net (code "60") (name "/SCL_WEST") (class "Default")
      (node (ref "SL2") (pin "3") (pinfunction "3_3") (pintype "passive"))
      (node (ref "U11") (pin "7") (pinfunction "SCL1_7") (pintype "bidirectional"))
    )
    (net (code "61") (name "/SDA_BOTTOM") (class "Default")
      (node (ref "SL6") (pin "4") (pinfunction "4_4") (pintype "passive"))
      (node (ref "U11") (pin "15") (pinfunction "SDA5_15") (pintype "bidirectional"))
    )
    (net (code "62") (name "/SDA_BUS") (class "Default")
      (node (ref "IC1") (pin "15") (pinfunction "SDA_15") (pintype "bidirectional"))
      (node (ref "U1") (pin "24") (pinfunction "SDA_24") (pintype "bidirectional"))
      (node (ref "U11") (pin "17") (pinfunction "SDA6_17") (pintype "bidirectional"))
      (node (ref "U13") (pin "1") (pinfunction "SDA_1") (pintype "bidirectional"))
      (node (ref "U14") (pin "16") (pinfunction "SDA_16") (pintype "bidirectional"))
      (node (ref "U2") (pin "1") (pinfunction "SDA_1") (pintype "bidirectional"))
      (node (ref "U7") (pin "6") (pinfunction "SDA_6") (pintype "bidirectional"))
      (node (ref "U9") (pin "6") (pinfunction "SDA_6") (pintype "bidirectional"))
      (node (ref "U9") (pin "7") (pinfunction "A0_7") (pintype "bidirectional"))
    )
    (net (code "63") (name "/SDA_CAM") (class "Default")
      (node (ref "ARDUCAM") (pin "7") (pinfunction "7_7") (pintype "passive"))
      (node (ref "U11") (pin "19") (pinfunction "SDA7_19") (pintype "bidirectional"))
    )
    (net (code "64") (name "/SDA_EAST") (class "Default")
      (node (ref "SL3") (pin "2") (pinfunction "2_2") (pintype "passive"))
      (node (ref "U11") (pin "8") (pinfunction "SDA2_8") (pintype "bidirectional"))
    )
    (net (code "65") (name "/SDA_NORTH") (class "Default")
      (node (ref "SL1") (pin "2") (pinfunction "2_2") (pintype "passive"))
      (node (ref "U11") (pin "4") (pinfunction "SDA0_4") (pintype "bidirectional"))
    )
    (net (code "66") (name "/SDA_SOUTH") (class "Default")
      (node (ref "SL4") (pin "2") (pinfunction "2_2") (pintype "passive"))
      (node (ref "U11") (pin "10") (pinfunction "SDA3_10") (pintype "bidirectional"))
    )
    (net (code "67") (name "/SDA_TOP") (class "Default")
      (node (ref "SL5") (pin "2") (pinfunction "2_2") (pintype "passive"))
      (node (ref "U11") (pin "13") (pinfunction "SDA4_13") (pintype "bidirectional"))
    )
    (net (code "68") (name "/SDA_UC") (class "Default")
      (node (ref "R3") (pin "2") (pinfunction "2_2") (pintype "passive"))
      (node (ref "U11") (pin "23") (pinfunction "SDA_23") (pintype "bidirectional"))
      (node (ref "U12") (pin "20") (pinfunction "PC1_20") (pintype "bidirectional"))
    )
    (net (code "69") (name "/SDA_WEST") (class "Default")
      (node (ref "SL2") (pin "2") (pinfunction "2_2") (pintype "passive"))
      (node (ref "U11") (pin "6") (pinfunction "SDA1_6") (pintype "bidirectional"))
    )
    (net (code "70") (name "/TRANSMITTER_PD") (class "Default")
      (node (ref "U12") (pin "15") (pinfunction "PD6_15") (pintype "bidirectional"))
      (node (ref "U3") (pin "6") (pinfunction "PD_6") (pintype "input"))
    )
    (net (code "71") (name "/TRANSMITTER_RX") (class "Default")
      (node (ref "U12") (pin "9") (pinfunction "PD0_9") (pintype "bidirectional"))
      (node (ref "U3") (pin "16") (pinfunction "RXD_16") (pintype "input"))
    )
    (net (code "72") (name "/TRANSMITTER_TX") (class "Default")
      (node (ref "U12") (pin "10") (pinfunction "PD1_10") (pintype "bidirectional"))
      (node (ref "U3") (pin "17") (pinfunction "TXD_17") (pintype "output"))
    )
    (net (code "73") (name "/TX_MICIN") (class "Default")
      (node (ref "U3") (pin "18") (pinfunction "MIC_IN_18") (pintype "input"))
      (node (ref "U5") (pin "3") (pinfunction "AF_OUT_3") (pintype "output"))
    )
    (net (code "74") (name "/TX_PTT") (class "Default")
      (node (ref "U3") (pin "5") (pinfunction "PTT_5") (pintype "input"))
      (node (ref "U5") (pin "1") (pinfunction "SQ_1") (pintype "output"))
    )
    (net (code "75") (name "/VIN-_SYS") (class "Default")
      (node (ref "C3") (pin "+") (pinfunction "+_+") (pintype "passive"))
      (node (ref "C52") (pin "1") (pinfunction "1_1") (pintype "passive"))
      (node (ref "R1") (pin "2") (pinfunction "2_2") (pintype "passive"))
      (node (ref "R36") (pin "1") (pinfunction "1_1") (pintype "passive"))
      (node (ref "R6") (pin "2") (pinfunction "2_2") (pintype "passive"))
      (node (ref "U4") (pin "1") (pinfunction "IN_1") (pintype "input"))
      (node (ref "U6") (pin "1") (pinfunction "VIN_1") (pintype "power_in"))
      (node (ref "U7") (pin "2") (pinfunction "VIN-_2") (pintype "bidirectional"))
    )
    (net (code "76") (name "/VIO") (class "Default")
      (node (ref "C11") (pin "1") (pinfunction "1_1") (pintype "passive"))
      (node (ref "U1") (pin "8") (pinfunction "VLOGIC_8") (pintype "bidirectional"))
    )
    (net (code "77") (name "/VOUT_REG_UC") (class "Default")
      (node (ref "C12") (pin "1") (pinfunction "1_1") (pintype "passive"))
      (node (ref "C2") (pin "+") (pinfunction "+_+") (pintype "passive"))
      (node (ref "C4") (pin "1") (pinfunction "1_1") (pintype "passive"))
      (node (ref "C56") (pin "2") (pinfunction "2_2") (pintype "passive"))
      (node (ref "IC1") (pin "2") (pinfunction "VCC_2") (pintype "power_in"))
      (node (ref "J3") (pin "2") (pinfunction "2_2") (pintype "passive"))
      (node (ref "R10") (pin "2") (pinfunction "2_2") (pintype "passive"))
      (node (ref "R16") (pin "2") (pinfunction "2_2") (pintype "passive"))
      (node (ref "R3") (pin "1") (pinfunction "1_1") (pintype "passive"))
      (node (ref "R4") (pin "1") (pinfunction "1_1") (pintype "passive"))
      (node (ref "U12") (pin "17") (pinfunction "VCC_3_17") (pintype "power_in"))
      (node (ref "U12") (pin "27") (pinfunction "AVCC_27") (pintype "power_in"))
      (node (ref "U12") (pin "38") (pinfunction "VCC_38") (pintype "power_in"))
      (node (ref "U12") (pin "5") (pinfunction "VCC_2_5") (pintype "power_in"))
      (node (ref "U4") (pin "5") (pinfunction "OUT_5") (pintype "passive"))
    )
    (net (code "78") (name "GND") (class "Default")
      (node (ref "ARDUCAM") (pin "5") (pinfunction "5_5") (pintype "passive"))
      (node (ref "C1") (pin "2") (pinfunction "2_2") (pintype "passive"))
      (node (ref "C10") (pin "2") (pinfunction "2_2") (pintype "passive"))
      (node (ref "C11") (pin "2") (pinfunction "2_2") (pintype "passive"))
      (node (ref "C12") (pin "2") (pinfunction "2_2") (pintype "passive"))
      (node (ref "C13") (pin "1") (pinfunction "1_1") (pintype "passive"))
      (node (ref "C14") (pin "1") (pinfunction "1_1") (pintype "passive"))
      (node (ref "C15") (pin "1") (pinfunction "1_1") (pintype "passive"))
      (node (ref "C16") (pin "2") (pinfunction "2_2") (pintype "passive"))
      (node (ref "C17") (pin "2") (pinfunction "2_2") (pintype "passive"))
      (node (ref "C18") (pin "2") (pinfunction "2_2") (pintype "passive"))
      (node (ref "C19") (pin "2") (pinfunction "2_2") (pintype "passive"))
      (node (ref "C2") (pin "-") (pinfunction "-_-") (pintype "passive"))
      (node (ref "C20") (pin "2") (pinfunction "2_2") (pintype "passive"))
      (node (ref "C21") (pin "2") (pinfunction "2_2") (pintype "passive"))
      (node (ref "C22") (pin "2") (pinfunction "2_2") (pintype "passive"))
      (node (ref "C23") (pin "2") (pinfunction "2_2") (pintype "passive"))
      (node (ref "C25") (pin "2") (pinfunction "2_2") (pintype "passive"))
      (node (ref "C26") (pin "2") (pinfunction "2_2") (pintype "passive"))
      (node (ref "C3") (pin "-") (pinfunction "-_-") (pintype "passive"))
      (node (ref "C4") (pin "2") (pinfunction "2_2") (pintype "passive"))
      (node (ref "C45") (pin "2") (pinfunction "2_2") (pintype "passive"))
      (node (ref "C5") (pin "2") (pinfunction "2_2") (pintype "passive"))
      (node (ref "C52") (pin "2") (pinfunction "2_2") (pintype "passive"))
      (node (ref "C55") (pin "1") (pinfunction "1_1") (pintype "passive"))
      (node (ref "C56") (pin "1") (pinfunction "1_1") (pintype "passive"))
      (node (ref "C6") (pin "1") (pinfunction "1_1") (pintype "passive"))
      (node (ref "C7") (pin "-") (pinfunction "-_-") (pintype "passive"))
      (node (ref "C8") (pin "-") (pinfunction "-_-") (pintype "passive"))
      (node (ref "C9") (pin "2") (pinfunction "2_2") (pintype "passive"))
      (node (ref "D1") (pin "A") (pinfunction "A_A") (pintype "passive"))
      (node (ref "D2") (pin "C") (pinfunction "C_C") (pintype "passive"))
      (node (ref "D3") (pin "C") (pinfunction "C_C") (pintype "passive"))
      (node (ref "D4") (pin "C") (pinfunction "C_C") (pintype "passive"))
      (node (ref "D5") (pin "C") (pinfunction "C_C") (pintype "passive"))
      (node (ref "D8") (pin "C") (pinfunction "C_C") (pintype "passive"))
      (node (ref "D9") (pin "C") (pinfunction "C_C") (pintype "passive"))
      (node (ref "IC1") (pin "13") (pinfunction "GND_13") (pintype "power_in"))
      (node (ref "J1") (pin "1") (pinfunction "1_1") (pintype "passive"))
      (node (ref "J16") (pin "1") (pinfunction "GND_1") (pintype "bidirectional"))
      (node (ref "J16") (pin "2") (pinfunction "GND_2") (pintype "bidirectional"))
      (node (ref "J2") (pin "1") (pinfunction "1_1") (pintype "passive"))
      (node (ref "J3") (pin "10") (pinfunction "10_10") (pintype "passive"))
      (node (ref "J3") (pin "4") (pinfunction "4_4") (pintype "passive"))
      (node (ref "J3") (pin "6") (pinfunction "6_6") (pintype "passive"))
      (node (ref "J3") (pin "8") (pinfunction "8_8") (pintype "passive"))
      (node (ref "J5") (pin "1") (pinfunction "GND_1") (pintype "bidirectional"))
      (node (ref "J5") (pin "2") (pinfunction "GND_2") (pintype "bidirectional"))
      (node (ref "J6") (pin "1") (pinfunction "GND_1") (pintype "bidirectional"))
      (node (ref "J6") (pin "2") (pinfunction "GND_2") (pintype "bidirectional"))
      (node (ref "R11") (pin "2") (pinfunction "2_2") (pintype "passive"))
      (node (ref "R51") (pin "2") (pinfunction "2_2") (pintype "passive"))
      (node (ref "R7") (pin "2") (pinfunction "2_2") (pintype "passive"))
      (node (ref "SL1") (pin "4") (pinfunction "4_4") (pintype "passive"))
      (node (ref "SL2") (pin "4") (pinfunction "4_4") (pintype "passive"))
      (node (ref "SL3") (pin "4") (pinfunction "4_4") (pintype "passive"))
      (node (ref "SL4") (pin "4") (pinfunction "4_4") (pintype "passive"))
      (node (ref "SL5") (pin "4") (pinfunction "4_4") (pintype "passive"))
      (node (ref "SL6") (pin "6") (pinfunction "6_6") (pintype "passive"))
      (node (ref "U$1") (pin "2") (pinfunction "GND_2") (pintype "bidirectional"))
      (node (ref "U$1") (pin "4") (pinfunction "GND2_4") (pintype "bidirectional"))
      (node (ref "U$1") (pin "5") (pinfunction "GND3_5") (pintype "bidirectional"))
      (node (ref "U$1") (pin "6") (pinfunction "GND/NC_6") (pintype "bidirectional"))
      (node (ref "U$1") (pin "7") (pinfunction "GND4_7") (pintype "bidirectional"))
      (node (ref "U1") (pin "11") (pinfunction "FSYNC_11") (pintype "bidirectional"))
      (node (ref "U1") (pin "18") (pinfunction "GND_18") (pintype "bidirectional"))
      (node (ref "U1") (pin "9") (pinfunction "AD0_9") (pintype "bidirectional"))
      (node (ref "U10") (pin "2") (pinfunction "GND_2") (pintype "input"))
      (node (ref "U11") (pin "1") (pinfunction "A0_1") (pintype "bidirectional"))
      (node (ref "U11") (pin "12") (pinfunction "GND_12") (pintype "bidirectional"))
      (node (ref "U11") (pin "2") (pinfunction "A1_2") (pintype "bidirectional"))
      (node (ref "U11") (pin "21") (pinfunction "A2_21") (pintype "bidirectional"))
      (node (ref "U12") (pin "18") (pinfunction "GND_3_18") (pintype "passive"))
      (node (ref "U12") (pin "28") (pinfunction "GND_4_28") (pintype "passive"))
      (node (ref "U12") (pin "39") (pinfunction "GND_39") (pintype "passive"))
      (node (ref "U12") (pin "6") (pinfunction "GND_2_6") (pintype "passive"))
      (node (ref "U13") (pin "4") (pinfunction "GND_4") (pintype "bidirectional"))
      (node (ref "U14") (pin "11") (pinfunction "GND_11") (pintype "bidirectional"))
      (node (ref "U14") (pin "9") (pinfunction "GND_9") (pintype "bidirectional"))
      (node (ref "U2") (pin "4") (pinfunction "GND_4") (pintype "bidirectional"))
      (node (ref "U3") (pin "10") (pinfunction "GND_10") (pintype "power_in"))
      (node (ref "U3") (pin "7") (pinfunction "H/L_7") (pintype "input"))
      (node (ref "U3") (pin "9") (pinfunction "GND_9") (pintype "power_in"))
      (node (ref "U4") (pin "2") (pinfunction "GND_2") (pintype "input"))
      (node (ref "U5") (pin "10") (pinfunction "GND_10") (pintype "power_in"))
      (node (ref "U5") (pin "7") (pinfunction "H/L_7") (pintype "input"))
      (node (ref "U5") (pin "9") (pinfunction "GND_9") (pintype "power_in"))
      (node (ref "U6") (pin "2") (pinfunction "GND_2") (pintype "power_in"))
      (node (ref "U7") (pin "3") (pinfunction "GND_3") (pintype "bidirectional"))
      (node (ref "U7") (pin "7") (pinfunction "A0_7") (pintype "bidirectional"))
      (node (ref "U7") (pin "8") (pinfunction "A1_8") (pintype "bidirectional"))
      (node (ref "U8") (pin "2") (pinfunction "GND_2") (pintype "power_in"))
      (node (ref "U9") (pin "3") (pinfunction "GND_3") (pintype "bidirectional"))
      (node (ref "Y2") (pin "2") (pinfunction "2_2") (pintype "passive"))
    )
    (net (code "79") (name "Net-(D1-PadC)") (class "Default")
      (node (ref "D1") (pin "C") (pinfunction "C_C") (pintype "passive"))
      (node (ref "R6") (pin "1") (pinfunction "1_1") (pintype "passive"))
    )
    (net (code "80") (name "Net-(D2-PadA)") (class "Default")
      (node (ref "D2") (pin "A") (pinfunction "A_A") (pintype "passive"))
      (node (ref "R1") (pin "1") (pinfunction "1_1") (pintype "passive"))
    )
    (net (code "81") (name "Net-(D3-PadA)") (class "Default")
      (node (ref "D3") (pin "A") (pinfunction "A_A") (pintype "passive"))
      (node (ref "R2") (pin "1") (pinfunction "1_1") (pintype "passive"))
    )
    (net (code "82") (name "Net-(D4-PadA)") (class "Default")
      (node (ref "D4") (pin "A") (pinfunction "A_A") (pintype "passive"))
      (node (ref "R17") (pin "1") (pinfunction "1_1") (pintype "passive"))
    )
    (net (code "83") (name "Net-(D5-PadA)") (class "Default")
      (node (ref "D5") (pin "A") (pinfunction "A_A") (pintype "passive"))
      (node (ref "R19") (pin "1") (pinfunction "1_1") (pintype "passive"))
    )
    (net (code "84") (name "Net-(D6-PadA)") (class "Default")
      (node (ref "D6") (pin "A") (pinfunction "A_A") (pintype "passive"))
      (node (ref "R44") (pin "1") (pinfunction "1_1") (pintype "passive"))
    )
    (net (code "85") (name "Net-(D8-PadA)") (class "Default")
      (node (ref "D8") (pin "A") (pinfunction "A_A") (pintype "passive"))
      (node (ref "R13") (pin "2") (pinfunction "2_2") (pintype "passive"))
    )
    (net (code "86") (name "Net-(D9-PadA)") (class "Default")
      (node (ref "D9") (pin "A") (pinfunction "A_A") (pintype "passive"))
      (node (ref "R20") (pin "2") (pinfunction "2_2") (pintype "passive"))
    )
    (net (code "87") (name "Net-(U1-CPOUT)") (class "Default")
      (node (ref "C9") (pin "1") (pinfunction "1_1") (pintype "passive"))
      (node (ref "U1") (pin "20") (pinfunction "CPOUT_20") (pintype "bidirectional"))
    )
    (net (code "88") (name "Net-(U1-REGOUT)") (class "Default")
      (node (ref "C1") (pin "1") (pinfunction "1_1") (pintype "passive"))
      (node (ref "U1") (pin "10") (pinfunction "REGOUT_10") (pintype "bidirectional"))
    )
    (net (code "89") (name "Net-(U1-VDD)") (class "Default")
      (node (ref "R53") (pin "1") (pinfunction "1_1") (pintype "passive"))
      (node (ref "U1") (pin "13") (pinfunction "VDD_13") (pintype "bidirectional"))
    )
    (net (code "90") (name "Net-(U2-A0)") (class "Default")
      (node (ref "R11") (pin "1") (pinfunction "1_1") (pintype "passive"))
      (node (ref "U2") (pin "7") (pinfunction "A0_7") (pintype "input"))
    )
    (net (code "91") (name "Net-(U2-A1)") (class "Default")
      (node (ref "R7") (pin "1") (pinfunction "1_1") (pintype "passive"))
      (node (ref "U2") (pin "6") (pinfunction "A1_6") (pintype "input"))
    )
    (net (code "92") (name "Net-(U2-A2)") (class "Default")
      (node (ref "R12") (pin "1") (pinfunction "1_1") (pintype "passive"))
      (node (ref "U2") (pin "5") (pinfunction "A2_5") (pintype "input"))
    )
    (net (code "93") (name "Net-(U2-OS)") (class "Default")
      (node (ref "R14") (pin "2") (pinfunction "2_2") (pintype "passive"))
      (node (ref "U2") (pin "3") (pinfunction "OS_3") (pintype "output"))
    )
    (net (code "94") (name "Net-(U4-BP)") (class "Default")
      (node (ref "C19") (pin "1") (pinfunction "1_1") (pintype "passive"))
      (node (ref "U4") (pin "4") (pinfunction "BP_4") (pintype "input"))
    )
    (net (code "95") (name "Net-(U6-EN)") (class "Default")
      (node (ref "R17") (pin "2") (pinfunction "2_2") (pintype "passive"))
      (node (ref "R18") (pin "2") (pinfunction "2_2") (pintype "passive"))
      (node (ref "U6") (pin "3") (pinfunction "EN_3") (pintype "input"))
    )
    (net (code "96") (name "Net-(U6-SW)") (class "Default")
      (node (ref "L3") (pin "1") (pinfunction "1_1") (pintype "passive"))
      (node (ref "U6") (pin "5") (pinfunction "SW_5") (pintype "output"))
    )
    (net (code "97") (name "Net-(U8-EN)") (class "Default")
      (node (ref "R2") (pin "2") (pinfunction "2_2") (pintype "passive"))
      (node (ref "R8") (pin "2") (pinfunction "2_2") (pintype "passive"))
      (node (ref "U8") (pin "3") (pinfunction "EN_3") (pintype "input"))
    )
    (net (code "98") (name "Net-(U8-SW)") (class "Default")
      (node (ref "L1") (pin "1") (pinfunction "1_1") (pintype "passive"))
      (node (ref "U8") (pin "5") (pinfunction "SW_5") (pintype "output"))
    )
    (net (code "99") (name "Net-(U10-BP)") (class "Default")
      (node (ref "C22") (pin "1") (pinfunction "1_1") (pintype "passive"))
      (node (ref "U10") (pin "4") (pinfunction "BP_4") (pintype "input"))
    )
    (net (code "100") (name "Net-(U12-XTAL1)") (class "Default")
      (node (ref "U12") (pin "8") (pinfunction "XTAL1_8") (pintype "input"))
      (node (ref "Y2") (pin "3") (pinfunction "3_3") (pintype "passive"))
    )
    (net (code "101") (name "Net-(U12-XTAL2)") (class "Default")
      (node (ref "U12") (pin "7") (pinfunction "XTAL2_7") (pintype "output"))
      (node (ref "Y2") (pin "1") (pinfunction "1_1") (pintype "passive"))
    )
    (net (code "102") (name "Net-(U13-A0)") (class "Default")
      (node (ref "R52") (pin "1") (pinfunction "1_1") (pintype "passive"))
      (node (ref "U13") (pin "7") (pinfunction "A0_7") (pintype "input"))
    )
    (net (code "103") (name "Net-(U13-A1)") (class "Default")
      (node (ref "R51") (pin "1") (pinfunction "1_1") (pintype "passive"))
      (node (ref "U13") (pin "6") (pinfunction "A1_6") (pintype "input"))
    )
    (net (code "104") (name "Net-(U13-A2)") (class "Default")
      (node (ref "R50") (pin "1") (pinfunction "1_1") (pintype "passive"))
      (node (ref "U13") (pin "5") (pinfunction "A2_5") (pintype "input"))
    )
    (net (code "105") (name "Net-(U13-OS)") (class "Default")
      (node (ref "R15") (pin "2") (pinfunction "2_2") (pintype "passive"))
      (node (ref "U13") (pin "3") (pinfunction "OS_3") (pintype "output"))
    )
    (net (code "106") (name "Net-(U14-C1)") (class "Default")
      (node (ref "C23") (pin "1") (pinfunction "1_1") (pintype "passive"))
      (node (ref "U14") (pin "10") (pinfunction "C1_10") (pintype "bidirectional"))
    )
    (net (code "107") (name "Net-(U14-SETC)") (class "Default")
      (node (ref "C24") (pin "2") (pinfunction "2_2") (pintype "passive"))
      (node (ref "U14") (pin "12") (pinfunction "SETC_12") (pintype "bidirectional"))
    )
    (net (code "108") (name "Net-(U14-SETP)") (class "Default")
      (node (ref "C24") (pin "1") (pinfunction "1_1") (pintype "passive"))
      (node (ref "U14") (pin "8") (pinfunction "SETP_8") (pintype "bidirectional"))
    )
    (net (code "109") (name "unconnected-(IC1-NC-Pad5)") (class "Default")
      (node (ref "IC1") (pin "5") (pinfunction "NC_5") (pintype "no_connect"))
    )
    (net (code "110") (name "unconnected-(IC1-NC1-Pad6)") (class "Default")
      (node (ref "IC1") (pin "6") (pinfunction "NC1_6") (pintype "no_connect"))
    )
    (net (code "111") (name "unconnected-(IC1-NC2-Pad7)") (class "Default")
      (node (ref "IC1") (pin "7") (pinfunction "NC2_7") (pintype "no_connect"))
    )
    (net (code "112") (name "unconnected-(IC1-NC3-Pad8)") (class "Default")
      (node (ref "IC1") (pin "8") (pinfunction "NC3_8") (pintype "no_connect"))
    )
    (net (code "113") (name "unconnected-(IC1-NC4-Pad9)") (class "Default")
      (node (ref "IC1") (pin "9") (pinfunction "NC4_9") (pintype "no_connect"))
    )
    (net (code "114") (name "unconnected-(IC1-NC5-Pad10)") (class "Default")
      (node (ref "IC1") (pin "10") (pinfunction "NC5_10") (pintype "no_connect"))
    )
    (net (code "115") (name "unconnected-(IC1-NC6-Pad11)") (class "Default")
      (node (ref "IC1") (pin "11") (pinfunction "NC6_11") (pintype "no_connect"))
    )
    (net (code "116") (name "unconnected-(IC1-NC7-Pad12)") (class "Default")
      (node (ref "IC1") (pin "12") (pinfunction "NC7_12") (pintype "no_connect"))
    )
    (net (code "117") (name "unconnected-(U1-AUX_CL-Pad7)") (class "Default")
      (node (ref "U1") (pin "7") (pinfunction "AUX_CL_7") (pintype "bidirectional"))
    )
    (net (code "118") (name "unconnected-(U1-AUX_DA-Pad6)") (class "Default")
      (node (ref "U1") (pin "6") (pinfunction "AUX_DA_6") (pintype "bidirectional"))
    )
    (net (code "119") (name "unconnected-(U1-CLKIN-Pad1)") (class "Default")
      (node (ref "U1") (pin "1") (pinfunction "CLKIN_1") (pintype "bidirectional"))
    )
    (net (code "120") (name "unconnected-(U1-INT-Pad12)") (class "Default")
      (node (ref "U1") (pin "12") (pinfunction "INT_12") (pintype "bidirectional"))
    )
    (net (code "121") (name "unconnected-(U11-#RESET-Pad3)") (class "Default")
      (node (ref "U11") (pin "3") (pinfunction "#RESET_3") (pintype "bidirectional"))
    )
    (net (code "122") (name "unconnected-(U14-DRDY-Pad15)") (class "Default")
      (node (ref "U14") (pin "15") (pinfunction "DRDY_15") (pintype "bidirectional"))
    )
    (net (code "123") (name "unconnected-(U14-NC-Pad3)") (class "Default")
      (node (ref "U14") (pin "3") (pinfunction "NC_3") (pintype "bidirectional"))
    )
    (net (code "124") (name "unconnected-(U14-NC-Pad5)") (class "Default")
      (node (ref "U14") (pin "5") (pinfunction "NC_5") (pintype "bidirectional"))
    )
    (net (code "125") (name "unconnected-(U14-NC-Pad6)") (class "Default")
      (node (ref "U14") (pin "6") (pinfunction "NC_6") (pintype "bidirectional"))
    )
    (net (code "126") (name "unconnected-(U14-NC-Pad7)") (class "Default")
      (node (ref "U14") (pin "7") (pinfunction "NC_7") (pintype "bidirectional"))
    )
    (net (code "127") (name "unconnected-(U14-NC-Pad14)") (class "Default")
      (node (ref "U14") (pin "14") (pinfunction "NC_14") (pintype "bidirectional"))
    )
  )
)
